# ArduOSD_Simple2222.net
KiCad netlist of a schematic drawn in EAGLE
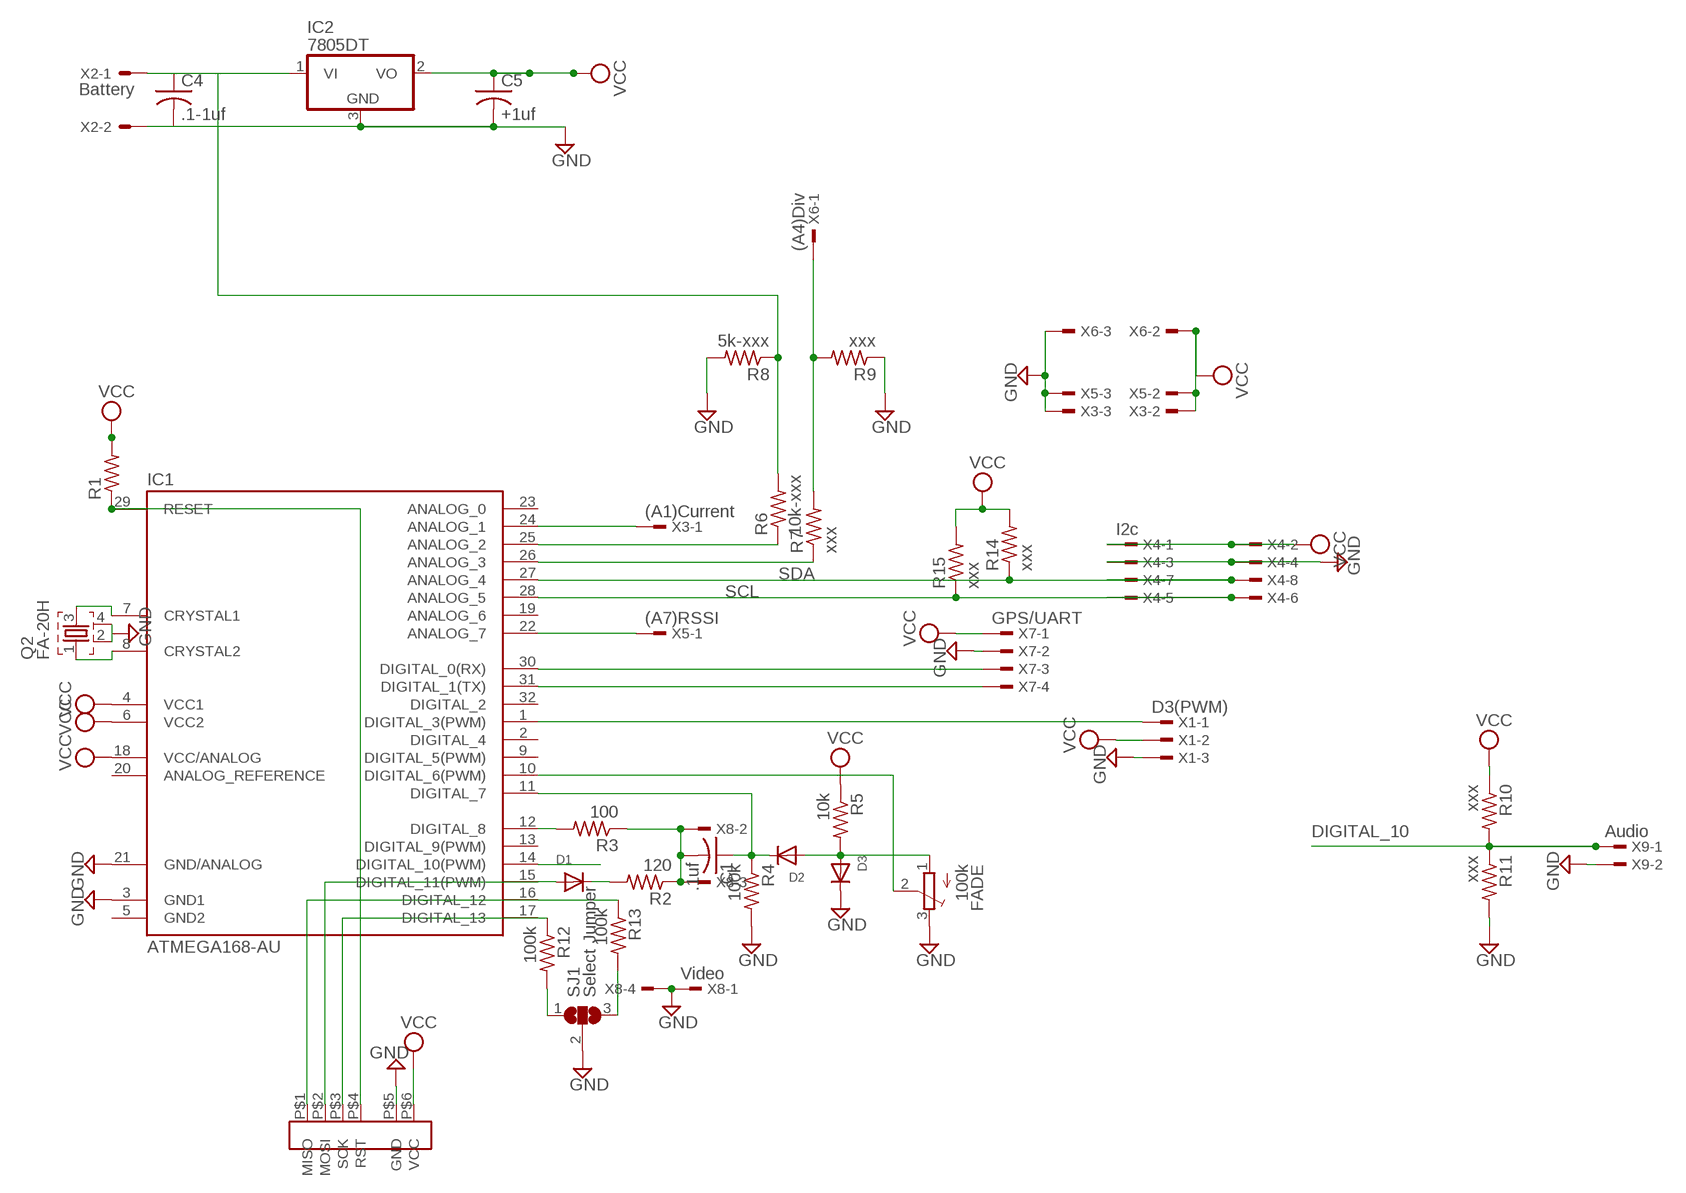
[diagram p0: schematic, sheet 1]

(export (version "E")
  (design (tool "Eeschema 10.0.6"))
  (components
    (comp (ref "C1")
      (value ".1uf")
      (footprint "eagle-import:C0805K")
      (libsource (lib "eagle-import") (part "C-USC0805K"))
    )
    (comp (ref "C4")
      (value ".1-1uf")
      (footprint "eagle-import:C0805K")
      (libsource (lib "eagle-import") (part "C-USC0805K"))
    )
    (comp (ref "C5")
      (value "+1uf")
      (footprint "eagle-import:C0805K")
      (libsource (lib "eagle-import") (part "C-USC0805K"))
    )
    (comp (ref "D1")
      (value "DIODESOT23_WAVE")
      (footprint "eagle-import:SOT23-W")
      (libsource (lib "eagle-import") (part "DIODESOT23_WAVE"))
    )
    (comp (ref "D2")
      (value "DIODESOT23_WAVE")
      (footprint "eagle-import:SOT23-W")
      (libsource (lib "eagle-import") (part "DIODESOT23_WAVE"))
    )
    (comp (ref "D3")
      (value "DIODESOT23_WAVE")
      (footprint "eagle-import:SOT23-W")
      (libsource (lib "eagle-import") (part "DIODESOT23_WAVE"))
    )
    (comp (ref "FADE")
      (value "100k")
      (footprint "eagle-import:TC33X")
      (libsource (lib "eagle-import") (part "TRIMPOTTC33X"))
    )
    (comp (ref "IC1")
      (value "ATMEGA168-AU")
      (footprint "eagle-import:TQFP32-08")
      (libsource (lib "eagle-import") (part "ATMEGA168-AU"))
    )
    (comp (ref "IC2")
      (value "7805DT")
      (footprint "eagle-import:TO252")
      (libsource (lib "eagle-import") (part "78DT05"))
    )
    (comp (ref "Q2")
      (value "FA-20H")
      (footprint "eagle-import:FA-20H")
      (libsource (lib "eagle-import") (part "FA-20H"))
    )
    (comp (ref "R1")
      (value "R-US_R0805")
      (footprint "eagle-import:R0805")
      (libsource (lib "eagle-import") (part "R-US_R0805"))
    )
    (comp (ref "R2")
      (value "120")
      (footprint "eagle-import:R0805")
      (libsource (lib "eagle-import") (part "R-US_R0805"))
    )
    (comp (ref "R3")
      (value "100")
      (footprint "eagle-import:R0805")
      (libsource (lib "eagle-import") (part "R-US_R0805"))
    )
    (comp (ref "R4")
      (value "100k")
      (footprint "eagle-import:R0805")
      (libsource (lib "eagle-import") (part "R-US_R0805"))
    )
    (comp (ref "R5")
      (value "10k")
      (footprint "eagle-import:R0805")
      (libsource (lib "eagle-import") (part "R-US_R0805"))
    )
    (comp (ref "R6")
      (value "10k-xxx")
      (footprint "eagle-import:R0805")
      (libsource (lib "eagle-import") (part "R-US_R0805"))
    )
    (comp (ref "R7")
      (value "xxx")
      (footprint "eagle-import:R0805")
      (libsource (lib "eagle-import") (part "R-US_R0805"))
    )
    (comp (ref "R8")
      (value "5k-xxx")
      (footprint "eagle-import:R0805")
      (libsource (lib "eagle-import") (part "R-US_R0805"))
    )
    (comp (ref "R9")
      (value "xxx")
      (footprint "eagle-import:R0805")
      (libsource (lib "eagle-import") (part "R-US_R0805"))
    )
    (comp (ref "R10")
      (value "xxx")
      (footprint "eagle-import:R0805")
      (libsource (lib "eagle-import") (part "R-US_R0805"))
    )
    (comp (ref "R11")
      (value "xxx")
      (footprint "eagle-import:R0805")
      (libsource (lib "eagle-import") (part "R-US_R0805"))
    )
    (comp (ref "R12")
      (value "100k")
      (footprint "eagle-import:R0805")
      (libsource (lib "eagle-import") (part "R-US_R0805"))
    )
    (comp (ref "R13")
      (value "100k")
      (footprint "eagle-import:R0805")
      (libsource (lib "eagle-import") (part "R-US_R0805"))
    )
    (comp (ref "R14")
      (value "xxx")
      (footprint "eagle-import:R0805")
      (libsource (lib "eagle-import") (part "R-US_R0805"))
    )
    (comp (ref "R15")
      (value "xxx")
      (footprint "eagle-import:R0805")
      (libsource (lib "eagle-import") (part "R-US_R0805"))
    )
    (comp (ref "SJ1")
      (value "Select Jumper")
      (footprint "eagle-import:SJ_2")
      (libsource (lib "eagle-import") (part "SJ2W"))
    )
    (comp (ref "U$1")
      (value "LIN_ISP")
      (footprint "eagle-import:LINEAR_ISP")
      (libsource (lib "eagle-import") (part "LIN_ISP"))
    )
    (comp (ref "X1")
      (value "D3(PWM)")
      (footprint "eagle-import:TSW-103-02-S-S")
      (fields (field (name "OC_FARNELL") "unknown") (field (name "OC_NEWARK") "unknown"))
      (libsource (lib "eagle-import") (part "TSW-103-02-S-S"))
    )
    (comp (ref "X2")
      (value "Battery")
      (footprint "eagle-import:22-23-2021")
      (fields (field (name "MF") "MOLEX") (field (name "MPN") "22-23-2021"))
      (libsource (lib "eagle-import") (part "22-23-2021"))
    )
    (comp (ref "X3")
      (value "(A1)Current")
      (footprint "eagle-import:TSW-103-02-S-S")
      (libsource (lib "eagle-import") (part "TSW-103-02-S-S"))
    )
    (comp (ref "X4")
      (value "I2c")
      (footprint "eagle-import:TSW-104-02-S-D-RA")
      (libsource (lib "eagle-import") (part "TSW-104-02-S-D-RA"))
    )
    (comp (ref "X5")
      (value "(A7)RSSI")
      (footprint "eagle-import:TSW-103-02-S-S")
      (libsource (lib "eagle-import") (part "TSW-103-02-S-S"))
    )
    (comp (ref "X6")
      (value "(A4)Div")
      (footprint "eagle-import:TSW-103-02-S-S")
      (fields (field (name "OC_FARNELL") "unknown") (field (name "OC_NEWARK") "unknown"))
      (libsource (lib "eagle-import") (part "TSW-103-02-S-S"))
    )
    (comp (ref "X7")
      (value "GPS/UART")
      (footprint "eagle-import:TSW-104-02-S-S-RA")
      (libsource (lib "eagle-import") (part "TSW-104-02-S-S-RA"))
    )
    (comp (ref "X8")
      (value "Video")
      (footprint "eagle-import:TSW-104-02-S-S-RA")
      (libsource (lib "eagle-import") (part "TSW-104-02-S-S-RA"))
    )
    (comp (ref "X9")
      (value "Audio")
      (footprint "eagle-import:TSW-102-02-S-S-RA")
      (fields (field (name "OC_FARNELL") "unknown") (field (name "OC_NEWARK") "unknown"))
      (libsource (lib "eagle-import") (part "TSW-102-02-S-S-RA"))
    )
  )
  (nets
    (net (code "1") (name "/DIGITAL_10") (class "Default")
      (node (ref "IC1") (pin "14") (pinfunction "DIGITAL_10(PWM)_14") (pintype "bidirectional"))
      (node (ref "R10") (pin "2") (pinfunction "2_2") (pintype "passive"))
      (node (ref "R11") (pin "1") (pinfunction "1_1") (pintype "passive"))
      (node (ref "X9") (pin "1") (pinfunction "1_1") (pintype "passive"))
    )
    (net (code "2") (name "/GND2") (class "Default")
      (node (ref "IC1") (pin "5") (pinfunction "GND2_5") (pintype "power_in"))
    )
    (net (code "3") (name "/SCL") (class "Default")
      (node (ref "IC1") (pin "28") (pinfunction "ANALOG_5_28") (pintype "bidirectional"))
      (node (ref "R15") (pin "1") (pinfunction "1_1") (pintype "passive"))
      (node (ref "X4") (pin "5") (pinfunction "1_5") (pintype "passive"))
      (node (ref "X4") (pin "6") (pinfunction "1_6") (pintype "passive"))
    )
    (net (code "4") (name "/SDA") (class "Default")
      (node (ref "IC1") (pin "27") (pinfunction "ANALOG_4_27") (pintype "bidirectional"))
      (node (ref "R14") (pin "1") (pinfunction "1_1") (pintype "passive"))
      (node (ref "X4") (pin "7") (pinfunction "1_7") (pintype "passive"))
      (node (ref "X4") (pin "8") (pinfunction "1_8") (pintype "passive"))
    )
    (net (code "5") (name "GND") (class "Default")
      (node (ref "C4") (pin "2") (pinfunction "2_2") (pintype "passive"))
      (node (ref "C5") (pin "2") (pinfunction "2_2") (pintype "passive"))
      (node (ref "D3") (pin "3") (pinfunction "C_3") (pintype "passive"))
      (node (ref "FADE") (pin "3") (pinfunction "E_3") (pintype "passive"))
      (node (ref "IC1") (pin "21") (pinfunction "GND/ANALOG_21") (pintype "power_in"))
      (node (ref "IC1") (pin "3") (pinfunction "GND1_3") (pintype "power_in"))
      (node (ref "IC2") (pin "3") (pinfunction "GND_3") (pintype "passive"))
      (node (ref "Q2") (pin "2") (pinfunction "2_2") (pintype "passive"))
      (node (ref "Q2") (pin "4") (pinfunction "4_4") (pintype "passive"))
      (node (ref "R11") (pin "2") (pinfunction "2_2") (pintype "passive"))
      (node (ref "R4") (pin "2") (pinfunction "2_2") (pintype "passive"))
      (node (ref "R8") (pin "2") (pinfunction "2_2") (pintype "passive"))
      (node (ref "R9") (pin "1") (pinfunction "1_1") (pintype "passive"))
      (node (ref "SJ1") (pin "2") (pinfunction "2_2") (pintype "passive"))
      (node (ref "U$1") (pin "P$5") (pinfunction "GND_P$5") (pintype "bidirectional"))
      (node (ref "X1") (pin "3") (pinfunction "1_3") (pintype "passive"))
      (node (ref "X2") (pin "2") (pinfunction "S_2") (pintype "passive"))
      (node (ref "X3") (pin "3") (pinfunction "1_3") (pintype "passive"))
      (node (ref "X4") (pin "3") (pinfunction "1_3") (pintype "passive"))
      (node (ref "X4") (pin "4") (pinfunction "1_4") (pintype "passive"))
      (node (ref "X5") (pin "3") (pinfunction "1_3") (pintype "passive"))
      (node (ref "X6") (pin "3") (pinfunction "1_3") (pintype "passive"))
      (node (ref "X7") (pin "2") (pinfunction "1_2") (pintype "passive"))
      (node (ref "X8") (pin "1") (pinfunction "1_1") (pintype "passive"))
      (node (ref "X8") (pin "4") (pinfunction "1_4") (pintype "passive"))
      (node (ref "X9") (pin "2") (pinfunction "1_2") (pintype "passive"))
    )
    (net (code "6") (name "Net-(D1-A)") (class "Default")
      (node (ref "D1") (pin "1") (pinfunction "A_1") (pintype "passive"))
      (node (ref "IC1") (pin "15") (pinfunction "DIGITAL_11(PWM)_15") (pintype "bidirectional"))
      (node (ref "U$1") (pin "P$2") (pinfunction "MOSI_P$2") (pintype "bidirectional"))
    )
    (net (code "7") (name "Net-(D1-C)") (class "Default")
      (node (ref "D1") (pin "3") (pinfunction "C_3") (pintype "passive"))
      (node (ref "R2") (pin "2") (pinfunction "2_2") (pintype "passive"))
    )
    (net (code "8") (name "Net-(D2-A)") (class "Default")
      (node (ref "D2") (pin "1") (pinfunction "A_1") (pintype "passive"))
      (node (ref "D3") (pin "1") (pinfunction "A_1") (pintype "passive"))
      (node (ref "FADE") (pin "1") (pinfunction "A_1") (pintype "passive"))
      (node (ref "R5") (pin "2") (pinfunction "2_2") (pintype "passive"))
    )
    (net (code "9") (name "Net-(D2-C)") (class "Default")
      (node (ref "C1") (pin "1") (pinfunction "1_1") (pintype "passive"))
      (node (ref "D2") (pin "3") (pinfunction "C_3") (pintype "passive"))
      (node (ref "IC1") (pin "11") (pinfunction "DIGITAL_7_11") (pintype "bidirectional"))
      (node (ref "R4") (pin "1") (pinfunction "1_1") (pintype "passive"))
    )
    (net (code "10") (name "Net-(FADE-S)") (class "Default")
      (node (ref "FADE") (pin "2") (pinfunction "S_2") (pintype "passive"))
      (node (ref "IC1") (pin "10") (pinfunction "DIGITAL_6(PWM)_10") (pintype "bidirectional"))
    )
    (net (code "11") (name "Net-(IC1-ANALOG_1)") (class "Default")
      (node (ref "IC1") (pin "24") (pinfunction "ANALOG_1_24") (pintype "bidirectional"))
      (node (ref "X3") (pin "1") (pinfunction "1_1") (pintype "passive"))
    )
    (net (code "12") (name "Net-(IC1-ANALOG_2)") (class "Default")
      (node (ref "IC1") (pin "25") (pinfunction "ANALOG_2_25") (pintype "bidirectional"))
      (node (ref "R6") (pin "1") (pinfunction "1_1") (pintype "passive"))
    )
    (net (code "13") (name "Net-(IC1-ANALOG_3)") (class "Default")
      (node (ref "IC1") (pin "26") (pinfunction "ANALOG_3_26") (pintype "bidirectional"))
      (node (ref "R7") (pin "1") (pinfunction "1_1") (pintype "passive"))
    )
    (net (code "14") (name "Net-(IC1-ANALOG_7)") (class "Default")
      (node (ref "IC1") (pin "22") (pinfunction "ANALOG_7_22") (pintype "passive"))
      (node (ref "X5") (pin "1") (pinfunction "1_1") (pintype "passive"))
    )
    (net (code "15") (name "Net-(IC1-CRYSTAL1)") (class "Default")
      (node (ref "IC1") (pin "7") (pinfunction "CRYSTAL1_7") (pintype "bidirectional"))
      (node (ref "Q2") (pin "3") (pinfunction "3_3") (pintype "passive"))
    )
    (net (code "16") (name "Net-(IC1-CRYSTAL2)") (class "Default")
      (node (ref "IC1") (pin "8") (pinfunction "CRYSTAL2_8") (pintype "bidirectional"))
      (node (ref "Q2") (pin "1") (pinfunction "1_1") (pintype "passive"))
    )
    (net (code "17") (name "Net-(IC1-DIGITAL_0(RX))") (class "Default")
      (node (ref "IC1") (pin "30") (pinfunction "DIGITAL_0(RX)_30") (pintype "bidirectional"))
      (node (ref "X7") (pin "3") (pinfunction "1_3") (pintype "passive"))
    )
    (net (code "18") (name "Net-(IC1-DIGITAL_1(TX))") (class "Default")
      (node (ref "IC1") (pin "31") (pinfunction "DIGITAL_1(TX)_31") (pintype "bidirectional"))
      (node (ref "X7") (pin "4") (pinfunction "1_4") (pintype "passive"))
    )
    (net (code "19") (name "Net-(IC1-DIGITAL_3(PWM))") (class "Default")
      (node (ref "IC1") (pin "1") (pinfunction "DIGITAL_3(PWM)_1") (pintype "bidirectional"))
      (node (ref "X1") (pin "1") (pinfunction "1_1") (pintype "passive"))
    )
    (net (code "20") (name "Net-(IC1-DIGITAL_8)") (class "Default")
      (node (ref "IC1") (pin "12") (pinfunction "DIGITAL_8_12") (pintype "bidirectional"))
      (node (ref "R3") (pin "2") (pinfunction "2_2") (pintype "passive"))
    )
    (net (code "21") (name "Net-(IC1-DIGITAL_12)") (class "Default")
      (node (ref "IC1") (pin "16") (pinfunction "DIGITAL_12_16") (pintype "bidirectional"))
      (node (ref "R13") (pin "1") (pinfunction "1_1") (pintype "passive"))
      (node (ref "U$1") (pin "P$1") (pinfunction "MISO_P$1") (pintype "bidirectional"))
    )
    (net (code "22") (name "Net-(IC1-DIGITAL_13)") (class "Default")
      (node (ref "IC1") (pin "17") (pinfunction "DIGITAL_13_17") (pintype "bidirectional"))
      (node (ref "R12") (pin "1") (pinfunction "1_1") (pintype "passive"))
      (node (ref "U$1") (pin "P$3") (pinfunction "SCK_P$3") (pintype "bidirectional"))
    )
    (net (code "23") (name "Net-(IC1-RESET)") (class "Default")
      (node (ref "IC1") (pin "29") (pinfunction "RESET_29") (pintype "bidirectional"))
      (node (ref "R1") (pin "1") (pinfunction "1_1") (pintype "passive"))
      (node (ref "U$1") (pin "P$4") (pinfunction "RST_P$4") (pintype "bidirectional"))
    )
    (net (code "24") (name "Net-(IC2-VI)") (class "Default")
      (node (ref "C4") (pin "1") (pinfunction "1_1") (pintype "passive"))
      (node (ref "IC2") (pin "1") (pinfunction "VI_1") (pintype "input"))
      (node (ref "R6") (pin "2") (pinfunction "2_2") (pintype "passive"))
      (node (ref "R8") (pin "1") (pinfunction "1_1") (pintype "passive"))
      (node (ref "X2") (pin "1") (pinfunction "S_1") (pintype "passive"))
    )
    (net (code "25") (name "Net-(R7-Pad2)") (class "Default")
      (node (ref "R7") (pin "2") (pinfunction "2_2") (pintype "passive"))
      (node (ref "R9") (pin "2") (pinfunction "2_2") (pintype "passive"))
      (node (ref "X6") (pin "1") (pinfunction "1_1") (pintype "passive"))
    )
    (net (code "26") (name "Net-(R12-Pad2)") (class "Default")
      (node (ref "R12") (pin "2") (pinfunction "2_2") (pintype "passive"))
      (node (ref "SJ1") (pin "1") (pinfunction "1_1") (pintype "passive"))
    )
    (net (code "27") (name "Net-(R13-Pad2)") (class "Default")
      (node (ref "R13") (pin "2") (pinfunction "2_2") (pintype "passive"))
      (node (ref "SJ1") (pin "3") (pinfunction "3_3") (pintype "passive"))
    )
    (net (code "28") (name "Net-(X8B-1)") (class "Default")
      (node (ref "C1") (pin "2") (pinfunction "2_2") (pintype "passive"))
      (node (ref "R2") (pin "1") (pinfunction "1_1") (pintype "passive"))
      (node (ref "R3") (pin "1") (pinfunction "1_1") (pintype "passive"))
      (node (ref "X8") (pin "2") (pinfunction "1_2") (pintype "passive"))
      (node (ref "X8") (pin "3") (pinfunction "1_3") (pintype "passive"))
    )
    (net (code "29") (name "VCC") (class "Default")
      (node (ref "C5") (pin "1") (pinfunction "1_1") (pintype "passive"))
      (node (ref "IC1") (pin "18") (pinfunction "VCC/ANALOG_18") (pintype "passive"))
      (node (ref "IC1") (pin "4") (pinfunction "VCC1_4") (pintype "power_in"))
      (node (ref "IC1") (pin "6") (pinfunction "VCC2_6") (pintype "power_in"))
      (node (ref "IC2") (pin "2") (pinfunction "VO_2") (pintype "passive"))
      (node (ref "R1") (pin "2") (pinfunction "2_2") (pintype "passive"))
      (node (ref "R10") (pin "1") (pinfunction "1_1") (pintype "passive"))
      (node (ref "R14") (pin "2") (pinfunction "2_2") (pintype "passive"))
      (node (ref "R15") (pin "2") (pinfunction "2_2") (pintype "passive"))
      (node (ref "R5") (pin "1") (pinfunction "1_1") (pintype "passive"))
      (node (ref "U$1") (pin "P$6") (pinfunction "VCC_P$6") (pintype "bidirectional"))
      (node (ref "X1") (pin "2") (pinfunction "1_2") (pintype "passive"))
      (node (ref "X3") (pin "2") (pinfunction "1_2") (pintype "passive"))
      (node (ref "X4") (pin "1") (pinfunction "1_1") (pintype "passive"))
      (node (ref "X4") (pin "2") (pinfunction "1_2") (pintype "passive"))
      (node (ref "X5") (pin "2") (pinfunction "1_2") (pintype "passive"))
      (node (ref "X6") (pin "2") (pinfunction "1_2") (pintype "passive"))
      (node (ref "X7") (pin "1") (pinfunction "1_1") (pintype "passive"))
    )
    (net (code "30") (name "unconnected-(IC1-ANALOG_0-Pad23)") (class "Default")
      (node (ref "IC1") (pin "23") (pinfunction "ANALOG_0_23") (pintype "bidirectional"))
    )
    (net (code "31") (name "unconnected-(IC1-ANALOG_6-Pad19)") (class "Default")
      (node (ref "IC1") (pin "19") (pinfunction "ANALOG_6_19") (pintype "passive"))
    )
    (net (code "32") (name "unconnected-(IC1-ANALOG_REFERENCE-Pad20)") (class "Default")
      (node (ref "IC1") (pin "20") (pinfunction "ANALOG_REFERENCE_20") (pintype "passive"))
    )
    (net (code "33") (name "unconnected-(IC1-DIGITAL_2-Pad32)") (class "Default")
      (node (ref "IC1") (pin "32") (pinfunction "DIGITAL_2_32") (pintype "bidirectional"))
    )
    (net (code "34") (name "unconnected-(IC1-DIGITAL_4-Pad2)") (class "Default")
      (node (ref "IC1") (pin "2") (pinfunction "DIGITAL_4_2") (pintype "bidirectional"))
    )
    (net (code "35") (name "unconnected-(IC1-DIGITAL_5(PWM)-Pad9)") (class "Default")
      (node (ref "IC1") (pin "9") (pinfunction "DIGITAL_5(PWM)_9") (pintype "bidirectional"))
    )
    (net (code "36") (name "unconnected-(IC1-DIGITAL_9(PWM)-Pad13)") (class "Default")
      (node (ref "IC1") (pin "13") (pinfunction "DIGITAL_9(PWM)_13") (pintype "bidirectional"))
    )
  )
)
